# EVK-IRIS-W1-MCULINK_USB_DCDC.net
KiCad netlist of a schematic drawn in Altium Designer
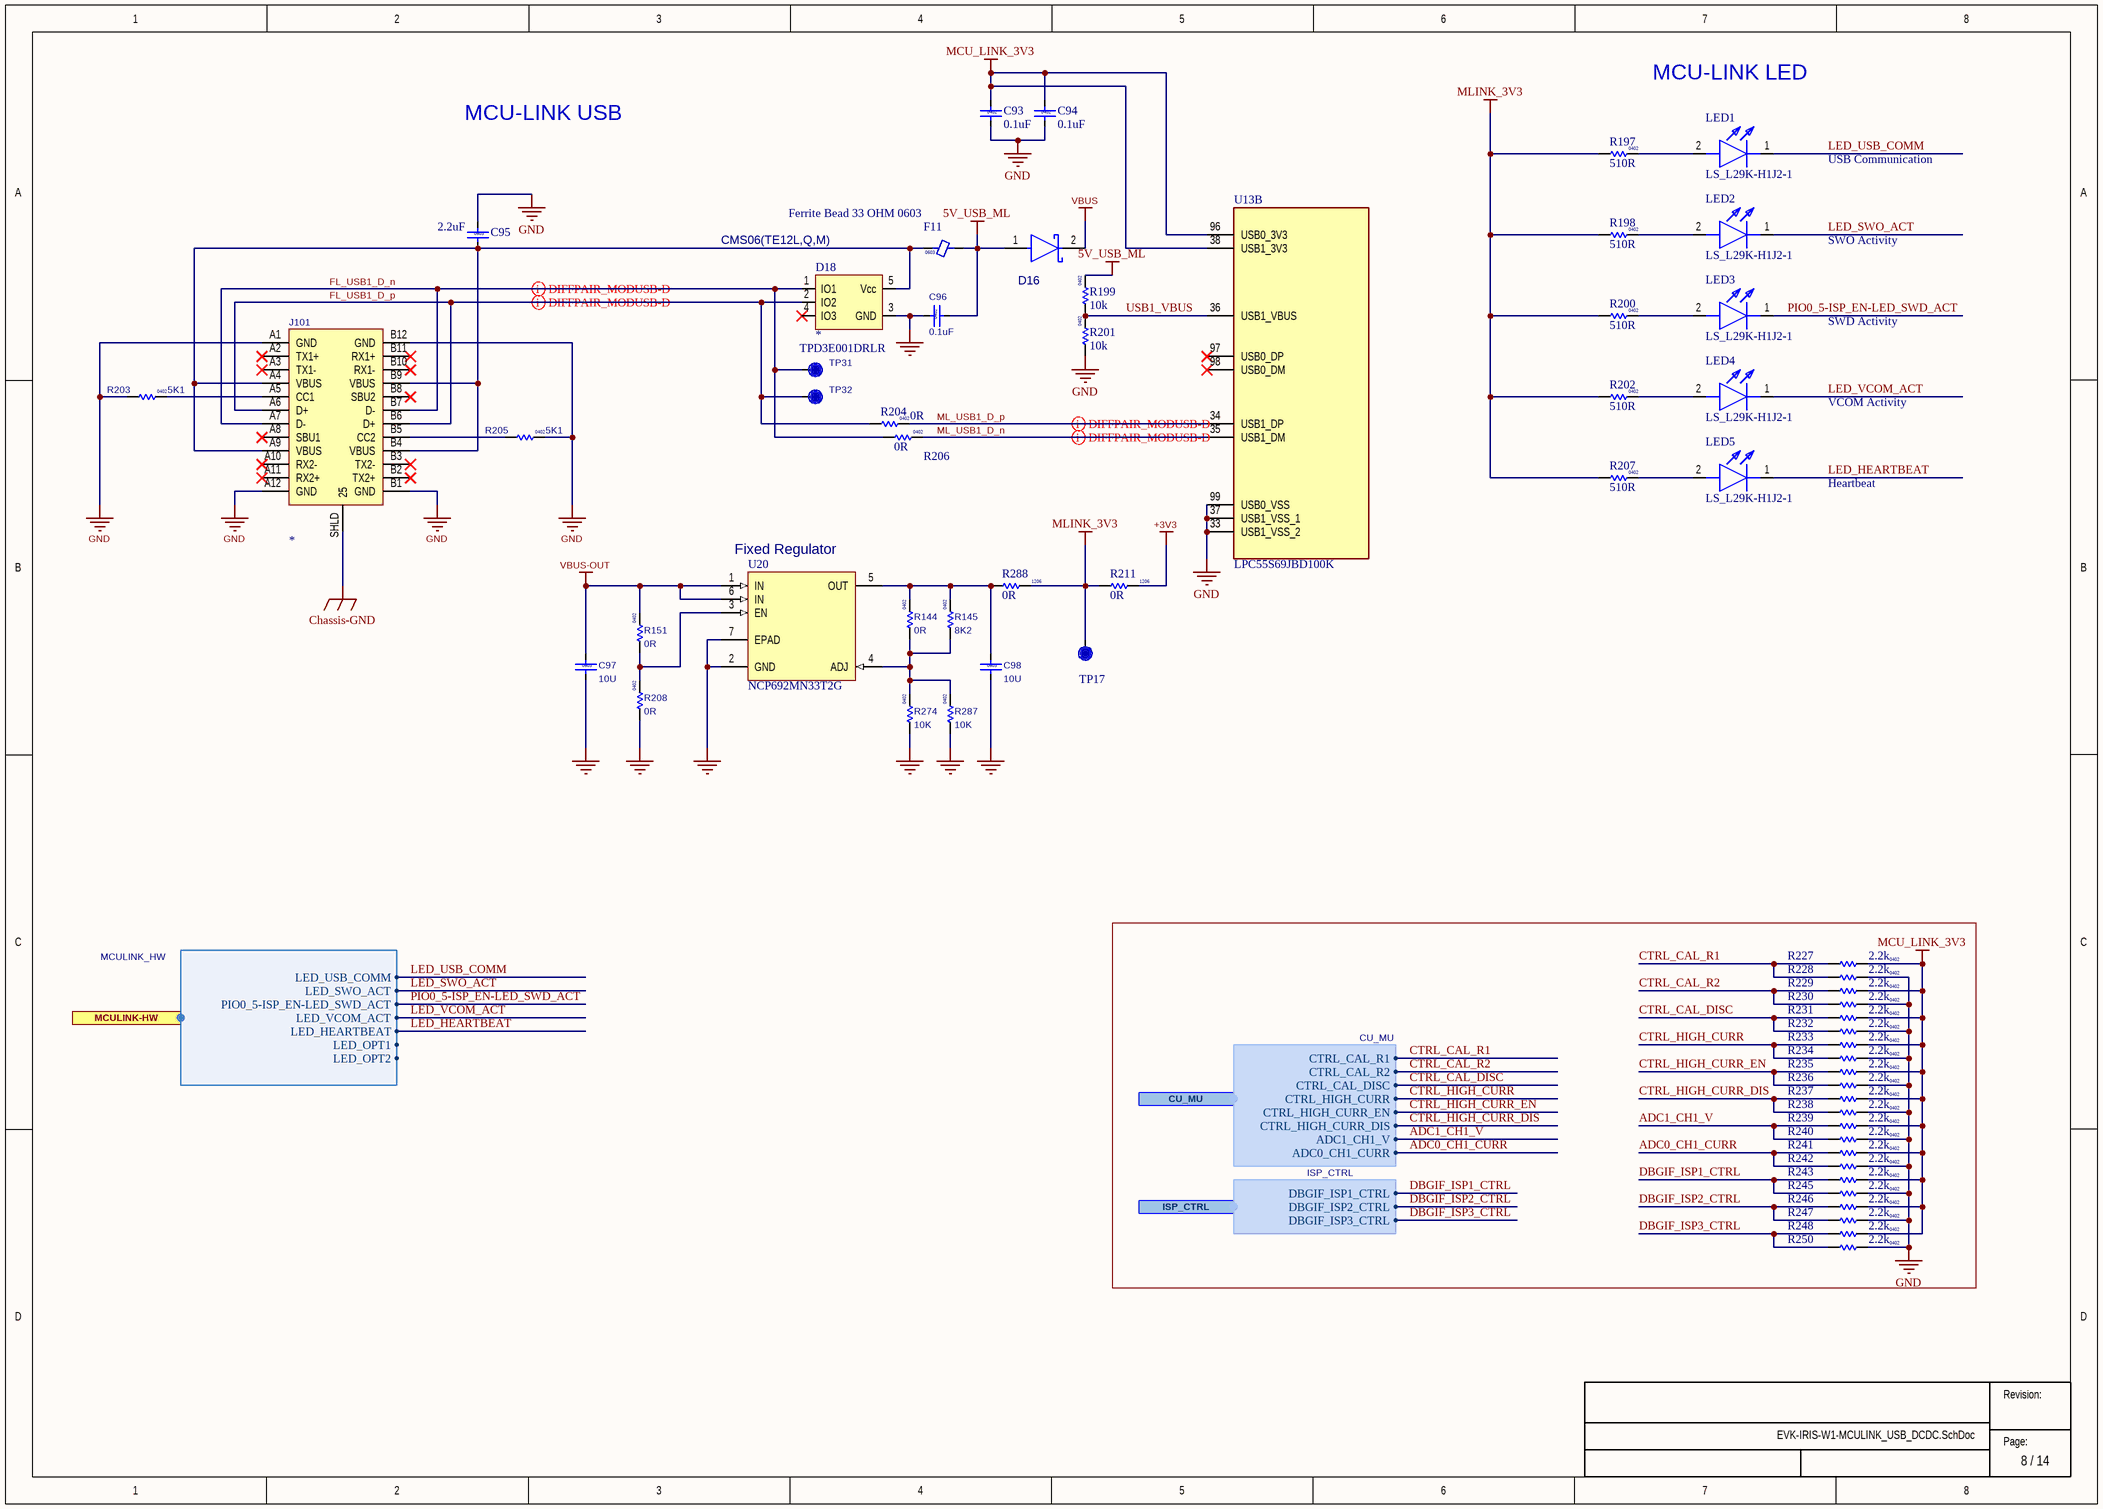
[diagram p0: EVK-IRIS-W1-MCULINK_USB_DCDC.SchDoc]

(export (version "E")
  (design (tool "Eeschema 10.0.6"))
  (components
    (comp (ref "C93")
      (value "0.1uF")
      (footprint "Cap 0402 HD")
      (description "Cap, Ceramic 0.1uF 10V 10% X5R 0402")
      (fields
        (field (name "SIZE") "0402")
        (field (name "PART NUMBER") "120-00016")
        (field (name "TOLERANCE") "+/- 10%")
      )
      (libsource (lib "Arena_Parts_DB_Lib") (part "Cap Chip"))
    )
    (comp (ref "C94")
      (value "0.1uF")
      (footprint "Cap 0402 HD")
      (description "Cap, Ceramic 0.1uF 10V 10% X5R 0402")
      (fields
        (field (name "SIZE") "0402")
        (field (name "PART NUMBER") "120-00016")
        (field (name "TOLERANCE") "+/- 10%")
      )
      (libsource (lib "Arena_Parts_DB_Lib") (part "Cap Chip"))
    )
    (comp (ref "C95")
      (value "2.2uF")
      (footprint "Cap 0603 HD")
      (description "Cap, Ceramic 2.2uF 10V 10% X5R 0603")
      (fields
        (field (name "SIZE") "0603")
        (field (name "PART NUMBER") "120-00004")
        (field (name "TOLERANCE") "+/- 10%")
      )
      (libsource (lib "Arena_Parts_DB_Lib") (part "Cap Chip"))
    )
    (comp (ref "C96")
      (value "0.1uF")
      (footprint "Cap 0402 HD")
      (description "Cap, Ceramic 0.1uF 10V 10% X5R 0402")
      (fields
        (field (name "SIZE") "0402")
        (field (name "PART NUMBER") "120-00016")
        (field (name "MANUFACTURER") "Murata Electronics North America")
      )
      (libsource (lib "Arena_Parts_DB_Lib") (part "Cap Chip"))
    )
    (comp (ref "C97")
      (value "10U")
      (footprint "Cap 0603 HD")
      (description "CAP CER X7R 0603 10U 20% 10V")
      (fields
        (field (name "SIZE") "0603")
        (field (name "PART NUMBER") "UBXH01-0000310")
        (field (name "TOLERANCE") "20%")
        (field (name "EDITOR") "michael.hein")
        (field (name "RELEASED BY") "martin.grasse")
      )
      (libsource (lib "UBX_Parts_DB_Lib") (part "Cap Chip"))
    )
    (comp (ref "C98")
      (value "10U")
      (footprint "Cap 0603 HD")
      (description "CAP CER X7R 0603 10U 20% 10V")
      (fields
        (field (name "SIZE") "0603")
        (field (name "PART NUMBER") "UBXH01-0000310")
        (field (name "TOLERANCE") "20%")
        (field (name "EDITOR") "michael.hein")
        (field (name "RELEASED BY") "martin.grasse")
      )
      (libsource (lib "UBX_Parts_DB_Lib") (part "Cap Chip"))
    )
    (comp (ref "D16")
      (value "CMS06(TE12L,Q,M)")
      (footprint "FP-M-FLAT-MFG")
      (description "Diode Schottky 30 V 2A Surface Mount M-FLAT (2.4x3.8)")
      (fields (field (name "MANUFACTURER") "Toshiba"))
      (libsource (lib "CMS06(TE12L,Q,M)") (part "360ad2f4ac25a952324d13796385471"))
    )
    (comp (ref "D18")
      (value "110-00018")
      (footprint "SOT-553")
      (description "TVS Diode, ESD High Speed 3-Channel Array, SOT-553")
      (fields
        (field (name "MANUFACTURER P/N") "*")
        (field (name "MANUFACTURER PART NUMBER 1") "TPD3E001DRLR")
        (field (name "VOLTAGE") "5.5V")
      )
      (libsource (lib "Arena_Parts_DB_Lib") (part "TPD3E001"))
    )
    (comp (ref "F11")
      (value "155-00012")
      (footprint "IND 0603")
      (description "FERRITE BEAD 33 OHM 0603 1LN")
      (fields
        (field (name "SIZE") "0603")
        (field (name "PART NAME") "Ferrite Bead 33 OHM 0603")
        (field (name "VOLTAGE") "None")
      )
      (libsource (lib "Arena_Parts_DB_Lib") (part "FB sm"))
    )
    (comp (ref "J101")
      (value "130-00150")
      (footprint "CON_USB-C-RA_W-6Tabs")
      (description "Connector, USB-C Receptacle, 24 Position, Surface Mount, Right Angle, Horizontal, 20V")
      (fields (field (name "MANUFACTURER P/N") "*") (field (name "VOLTAGE") "20V"))
      (libsource (lib "Arena_Parts_DB_Lib") (part "USB-24Pin_W-Shield"))
    )
    (comp (ref "LED1")
      (value "LS_L29K-H1J2-1")
      (footprint "SamacSys:SMT-0603")
      (description "LED")
      (fields
        (field (name "MANUFACTURER_PART_NUMBER") "LS L29K-H1J2-1")
        (field (name "MOUSER PART NUMBER") "720-LSL29K-H1J2-1-Z")
      )
      (libsource (lib "*") (part "LS_L29K-H1J2-1"))
    )
    (comp (ref "LED2")
      (value "LS_L29K-H1J2-1")
      (footprint "SamacSys:SMT-0603")
      (description "LED")
      (fields
        (field (name "MANUFACTURER_PART_NUMBER") "LS L29K-H1J2-1")
        (field (name "MOUSER PART NUMBER") "720-LSL29K-H1J2-1-Z")
      )
      (libsource (lib "*") (part "LS_L29K-H1J2-1"))
    )
    (comp (ref "LED3")
      (value "LS_L29K-H1J2-1")
      (footprint "SamacSys:SMT-0603")
      (description "LED")
      (fields
        (field (name "MANUFACTURER_PART_NUMBER") "LS L29K-H1J2-1")
        (field (name "MOUSER PART NUMBER") "720-LSL29K-H1J2-1-Z")
      )
      (libsource (lib "*") (part "LS_L29K-H1J2-1"))
    )
    (comp (ref "LED4")
      (value "LS_L29K-H1J2-1")
      (footprint "SamacSys:SMT-0603")
      (description "LED")
      (fields
        (field (name "MANUFACTURER_PART_NUMBER") "LS L29K-H1J2-1")
        (field (name "MOUSER PART NUMBER") "720-LSL29K-H1J2-1-Z")
      )
      (libsource (lib "*") (part "LS_L29K-H1J2-1"))
    )
    (comp (ref "LED5")
      (value "LS_L29K-H1J2-1")
      (footprint "SamacSys:SMT-0603")
      (description "LED")
      (fields
        (field (name "MANUFACTURER_PART_NUMBER") "LS L29K-H1J2-1")
        (field (name "MOUSER PART NUMBER") "720-LSL29K-H1J2-1-Z")
      )
      (libsource (lib "*") (part "LS_L29K-H1J2-1"))
    )
    (comp (ref "R144")
      (value "0R")
      (footprint "RES 0402 HD")
      (description "RES THICK FILM CHIP 0402 0R 0 100mW")
      (fields
        (field (name "SIZE") "0402")
        (field (name "PART NUMBER") "UBXH18-0003002")
        (field (name "TOLERANCE") "0")
        (field (name "EDITOR") "charlotte.biber")
        (field (name "RELEASED BY") "peter.mueller")
      )
      (libsource (lib "UBX_Parts_DB_Lib") (part "Res sm"))
    )
    (comp (ref "R145")
      (value "8K2")
      (footprint "RES 0402 HD")
      (description "RES THICK FILM CHIP 0402 8K2 1% 63mW")
      (fields
        (field (name "SIZE") "0402")
        (field (name "PART NUMBER") "UBXH18-0000138")
        (field (name "TOLERANCE") "1%")
        (field (name "EDITOR") "matej.budin")
        (field (name "RELEASED BY") "pasquale.scorca")
      )
      (libsource (lib "UBX_Parts_DB_Lib") (part "Res sm"))
    )
    (comp (ref "R151")
      (value "0R")
      (footprint "RES 0402 HD")
      (description "RES THICK FILM CHIP 0402 0R 0 100mW")
      (fields
        (field (name "SIZE") "0402")
        (field (name "PART NUMBER") "UBXH18-0003002")
        (field (name "TOLERANCE") "0")
        (field (name "EDITOR") "charlotte.biber")
        (field (name "RELEASED BY") "peter.mueller")
      )
      (libsource (lib "UBX_Parts_DB_Lib") (part "Res sm"))
    )
    (comp (ref "R197")
      (value "510R")
      (footprint "RES 0402 HD")
      (description "RES THICK FILM CHIP 0402 510R 5% 100mW")
      (fields
        (field (name "SIZE") "0402")
        (field (name "PART NUMBER") "UBXH18-0008042")
        (field (name "TOLERANCE") "5%")
        (field (name "EDITOR") "peter.mueller")
      )
      (libsource (lib "UBX_Parts_DB_Lib") (part "Res sm"))
    )
    (comp (ref "R198")
      (value "510R")
      (footprint "RES 0402 HD")
      (description "RES THICK FILM CHIP 0402 510R 5% 100mW")
      (fields
        (field (name "SIZE") "0402")
        (field (name "PART NUMBER") "UBXH18-0008042")
        (field (name "TOLERANCE") "5%")
        (field (name "EDITOR") "peter.mueller")
      )
      (libsource (lib "UBX_Parts_DB_Lib") (part "Res sm"))
    )
    (comp (ref "R199")
      (value "10k")
      (footprint "RES 0402 HD")
      (description "Resistor 10k ohm 1% 1/16W, 0402")
      (fields
        (field (name "SIZE") "0402")
        (field (name "PART NUMBER") "180-00024")
        (field (name "POWER") "1/16W")
      )
      (libsource (lib "Arena_Parts_DB_Lib") (part "Res sm"))
    )
    (comp (ref "R200")
      (value "510R")
      (footprint "RES 0402 HD")
      (description "RES THICK FILM CHIP 0402 510R 5% 100mW")
      (fields
        (field (name "SIZE") "0402")
        (field (name "PART NUMBER") "UBXH18-0008042")
        (field (name "TOLERANCE") "5%")
        (field (name "EDITOR") "peter.mueller")
      )
      (libsource (lib "UBX_Parts_DB_Lib") (part "Res sm"))
    )
    (comp (ref "R201")
      (value "10k")
      (footprint "RES 0402 HD")
      (description "Resistor 10k ohm 1% 1/16W, 0402")
      (fields
        (field (name "SIZE") "0402")
        (field (name "PART NUMBER") "180-00024")
        (field (name "POWER") "1/16W")
      )
      (libsource (lib "Arena_Parts_DB_Lib") (part "Res sm"))
    )
    (comp (ref "R202")
      (value "510R")
      (footprint "RES 0402 HD")
      (description "RES THICK FILM CHIP 0402 510R 5% 100mW")
      (fields
        (field (name "SIZE") "0402")
        (field (name "PART NUMBER") "UBXH18-0008042")
        (field (name "TOLERANCE") "5%")
        (field (name "EDITOR") "peter.mueller")
      )
      (libsource (lib "UBX_Parts_DB_Lib") (part "Res sm"))
    )
    (comp (ref "R203")
      (value "5K1")
      (footprint "RES 0402 HD")
      (description "RES THICK FILM CHIP 0402 5K1 5% 100mW")
      (fields
        (field (name "SIZE") "0402")
        (field (name "PART NUMBER") "UBXH18-0008066")
        (field (name "TOLERANCE") "5%")
        (field (name "EDITOR") "alvaro.nussbaum")
        (field (name "RELEASED BY") "roland.rust")
      )
      (libsource (lib "UBX_Parts_DB_Lib") (part "Res sm"))
    )
    (comp (ref "R204")
      (value "0R")
      (footprint "RES 0402 HD")
      (description "RES THICK FILM CHIP 0402 0R 0 100mW")
      (fields
        (field (name "SIZE") "0402")
        (field (name "PART NUMBER") "UBXH18-0003002")
        (field (name "TOLERANCE") "0")
        (field (name "EDITOR") "charlotte.biber")
        (field (name "RELEASED BY") "peter.mueller")
      )
      (libsource (lib "UBX_Parts_DB_Lib") (part "Res sm"))
    )
    (comp (ref "R205")
      (value "5K1")
      (footprint "RES 0402 HD")
      (description "RES THICK FILM CHIP 0402 5K1 5% 100mW")
      (fields
        (field (name "SIZE") "0402")
        (field (name "PART NUMBER") "UBXH18-0008066")
        (field (name "TOLERANCE") "5%")
        (field (name "EDITOR") "alvaro.nussbaum")
        (field (name "RELEASED BY") "roland.rust")
      )
      (libsource (lib "UBX_Parts_DB_Lib") (part "Res sm"))
    )
    (comp (ref "R206")
      (value "0R")
      (footprint "RES 0402 HD")
      (description "RES THICK FILM CHIP 0402 0R 0 100mW")
      (fields
        (field (name "SIZE") "0402")
        (field (name "PART NUMBER") "UBXH18-0003002")
        (field (name "TOLERANCE") "0")
        (field (name "EDITOR") "charlotte.biber")
        (field (name "RELEASED BY") "peter.mueller")
      )
      (libsource (lib "UBX_Parts_DB_Lib") (part "Res sm"))
    )
    (comp (ref "R207")
      (value "510R")
      (footprint "RES 0402 HD")
      (description "RES THICK FILM CHIP 0402 510R 5% 100mW")
      (fields
        (field (name "SIZE") "0402")
        (field (name "PART NUMBER") "UBXH18-0008042")
        (field (name "TOLERANCE") "5%")
        (field (name "EDITOR") "peter.mueller")
      )
      (libsource (lib "UBX_Parts_DB_Lib") (part "Res sm"))
    )
    (comp (ref "R208")
      (value "0R")
      (footprint "RES 0402 HD")
      (description "RES THICK FILM CHIP 0402 0R 0 100mW")
      (fields
        (field (name "SIZE") "0402")
        (field (name "PART NUMBER") "UBXH18-0003002")
        (field (name "TOLERANCE") "0")
        (field (name "EDITOR") "charlotte.biber")
        (field (name "RELEASED BY") "peter.mueller")
      )
      (libsource (lib "UBX_Parts_DB_Lib") (part "Res sm"))
    )
    (comp (ref "R211")
      (value "0R")
      (footprint "RES 1206")
      (description "RES THICK FILM CHIP 1206 0R 0 2A")
      (fields
        (field (name "SIZE") "1206")
        (field (name "PART NUMBER") "UBXH18-0000020")
        (field (name "TOLERANCE") "0")
        (field (name "EDITOR") "massimo.vlacci")
        (field (name "RELEASED BY") "erian.bezhani")
      )
      (libsource (lib "UBX_Parts_DB_Lib") (part "Res sm"))
    )
    (comp (ref "R227")
      (value "2.2k")
      (footprint "RES 0402 HD")
      (description "Resistor, 2.2Kohm, 1%, 1/16W, 0402")
      (fields
        (field (name "SIZE") "0402")
        (field (name "PART NUMBER") "180-00023")
        (field (name "POWER") "1/16W")
      )
      (libsource (lib "Arena_Parts_DB_Lib") (part "Res sm"))
    )
    (comp (ref "R228")
      (value "2.2k")
      (footprint "RES 0402 HD")
      (description "Resistor, 2.2Kohm, 1%, 1/16W, 0402")
      (fields
        (field (name "SIZE") "0402")
        (field (name "PART NUMBER") "180-00023")
        (field (name "POWER") "1/16W")
      )
      (libsource (lib "Arena_Parts_DB_Lib") (part "Res sm"))
    )
    (comp (ref "R229")
      (value "2.2k")
      (footprint "RES 0402 HD")
      (description "Resistor, 2.2Kohm, 1%, 1/16W, 0402")
      (fields
        (field (name "SIZE") "0402")
        (field (name "PART NUMBER") "180-00023")
        (field (name "POWER") "1/16W")
      )
      (libsource (lib "Arena_Parts_DB_Lib") (part "Res sm"))
    )
    (comp (ref "R230")
      (value "2.2k")
      (footprint "RES 0402 HD")
      (description "Resistor, 2.2Kohm, 1%, 1/16W, 0402")
      (fields
        (field (name "SIZE") "0402")
        (field (name "PART NUMBER") "180-00023")
        (field (name "POWER") "1/16W")
      )
      (libsource (lib "Arena_Parts_DB_Lib") (part "Res sm"))
    )
    (comp (ref "R231")
      (value "2.2k")
      (footprint "RES 0402 HD")
      (description "Resistor, 2.2Kohm, 1%, 1/16W, 0402")
      (fields
        (field (name "SIZE") "0402")
        (field (name "PART NUMBER") "180-00023")
        (field (name "POWER") "1/16W")
      )
      (libsource (lib "Arena_Parts_DB_Lib") (part "Res sm"))
    )
    (comp (ref "R232")
      (value "2.2k")
      (footprint "RES 0402 HD")
      (description "Resistor, 2.2Kohm, 1%, 1/16W, 0402")
      (fields
        (field (name "SIZE") "0402")
        (field (name "PART NUMBER") "180-00023")
        (field (name "POWER") "1/16W")
      )
      (libsource (lib "Arena_Parts_DB_Lib") (part "Res sm"))
    )
    (comp (ref "R233")
      (value "2.2k")
      (footprint "RES 0402 HD")
      (description "Resistor, 2.2Kohm, 1%, 1/16W, 0402")
      (fields
        (field (name "SIZE") "0402")
        (field (name "PART NUMBER") "180-00023")
        (field (name "POWER") "1/16W")
      )
      (libsource (lib "Arena_Parts_DB_Lib") (part "Res sm"))
    )
    (comp (ref "R234")
      (value "2.2k")
      (footprint "RES 0402 HD")
      (description "Resistor, 2.2Kohm, 1%, 1/16W, 0402")
      (fields
        (field (name "SIZE") "0402")
        (field (name "PART NUMBER") "180-00023")
        (field (name "POWER") "1/16W")
      )
      (libsource (lib "Arena_Parts_DB_Lib") (part "Res sm"))
    )
    (comp (ref "R235")
      (value "2.2k")
      (footprint "RES 0402 HD")
      (description "Resistor, 2.2Kohm, 1%, 1/16W, 0402")
      (fields
        (field (name "SIZE") "0402")
        (field (name "PART NUMBER") "180-00023")
        (field (name "POWER") "1/16W")
      )
      (libsource (lib "Arena_Parts_DB_Lib") (part "Res sm"))
    )
    (comp (ref "R236")
      (value "2.2k")
      (footprint "RES 0402 HD")
      (description "Resistor, 2.2Kohm, 1%, 1/16W, 0402")
      (fields
        (field (name "SIZE") "0402")
        (field (name "PART NUMBER") "180-00023")
        (field (name "POWER") "1/16W")
      )
      (libsource (lib "Arena_Parts_DB_Lib") (part "Res sm"))
    )
    (comp (ref "R237")
      (value "2.2k")
      (footprint "RES 0402 HD")
      (description "Resistor, 2.2Kohm, 1%, 1/16W, 0402")
      (fields
        (field (name "SIZE") "0402")
        (field (name "PART NUMBER") "180-00023")
        (field (name "POWER") "1/16W")
      )
      (libsource (lib "Arena_Parts_DB_Lib") (part "Res sm"))
    )
    (comp (ref "R238")
      (value "2.2k")
      (footprint "RES 0402 HD")
      (description "Resistor, 2.2Kohm, 1%, 1/16W, 0402")
      (fields
        (field (name "SIZE") "0402")
        (field (name "PART NUMBER") "180-00023")
        (field (name "POWER") "1/16W")
      )
      (libsource (lib "Arena_Parts_DB_Lib") (part "Res sm"))
    )
    (comp (ref "R239")
      (value "2.2k")
      (footprint "RES 0402 HD")
      (description "Resistor, 2.2Kohm, 1%, 1/16W, 0402")
      (fields
        (field (name "SIZE") "0402")
        (field (name "PART NUMBER") "180-00023")
        (field (name "POWER") "1/16W")
      )
      (libsource (lib "Arena_Parts_DB_Lib") (part "Res sm"))
    )
    (comp (ref "R240")
      (value "2.2k")
      (footprint "RES 0402 HD")
      (description "Resistor, 2.2Kohm, 1%, 1/16W, 0402")
      (fields
        (field (name "SIZE") "0402")
        (field (name "PART NUMBER") "180-00023")
        (field (name "POWER") "1/16W")
      )
      (libsource (lib "Arena_Parts_DB_Lib") (part "Res sm"))
    )
    (comp (ref "R241")
      (value "2.2k")
      (footprint "RES 0402 HD")
      (description "Resistor, 2.2Kohm, 1%, 1/16W, 0402")
      (fields
        (field (name "SIZE") "0402")
        (field (name "PART NUMBER") "180-00023")
        (field (name "POWER") "1/16W")
      )
      (libsource (lib "Arena_Parts_DB_Lib") (part "Res sm"))
    )
    (comp (ref "R242")
      (value "2.2k")
      (footprint "RES 0402 HD")
      (description "Resistor, 2.2Kohm, 1%, 1/16W, 0402")
      (fields
        (field (name "SIZE") "0402")
        (field (name "PART NUMBER") "180-00023")
        (field (name "POWER") "1/16W")
      )
      (libsource (lib "Arena_Parts_DB_Lib") (part "Res sm"))
    )
    (comp (ref "R243")
      (value "2.2k")
      (footprint "RES 0402 HD")
      (description "Resistor, 2.2Kohm, 1%, 1/16W, 0402")
      (fields
        (field (name "SIZE") "0402")
        (field (name "PART NUMBER") "180-00023")
        (field (name "POWER") "1/16W")
      )
      (libsource (lib "Arena_Parts_DB_Lib") (part "Res sm"))
    )
    (comp (ref "R245")
      (value "2.2k")
      (footprint "RES 0402 HD")
      (description "Resistor, 2.2Kohm, 1%, 1/16W, 0402")
      (fields
        (field (name "SIZE") "0402")
        (field (name "PART NUMBER") "180-00023")
        (field (name "POWER") "1/16W")
      )
      (libsource (lib "Arena_Parts_DB_Lib") (part "Res sm"))
    )
    (comp (ref "R246")
      (value "2.2k")
      (footprint "RES 0402 HD")
      (description "Resistor, 2.2Kohm, 1%, 1/16W, 0402")
      (fields
        (field (name "SIZE") "0402")
        (field (name "PART NUMBER") "180-00023")
        (field (name "POWER") "1/16W")
      )
      (libsource (lib "Arena_Parts_DB_Lib") (part "Res sm"))
    )
    (comp (ref "R247")
      (value "2.2k")
      (footprint "RES 0402 HD")
      (description "Resistor, 2.2Kohm, 1%, 1/16W, 0402")
      (fields
        (field (name "SIZE") "0402")
        (field (name "PART NUMBER") "180-00023")
        (field (name "POWER") "1/16W")
      )
      (libsource (lib "Arena_Parts_DB_Lib") (part "Res sm"))
    )
    (comp (ref "R248")
      (value "2.2k")
      (footprint "RES 0402 HD")
      (description "Resistor, 2.2Kohm, 1%, 1/16W, 0402")
      (fields
        (field (name "SIZE") "0402")
        (field (name "PART NUMBER") "180-00023")
        (field (name "POWER") "1/16W")
      )
      (libsource (lib "Arena_Parts_DB_Lib") (part "Res sm"))
    )
    (comp (ref "R250")
      (value "2.2k")
      (footprint "RES 0402 HD")
      (description "Resistor, 2.2Kohm, 1%, 1/16W, 0402")
      (fields
        (field (name "SIZE") "0402")
        (field (name "PART NUMBER") "180-00023")
        (field (name "POWER") "1/16W")
      )
      (libsource (lib "Arena_Parts_DB_Lib") (part "Res sm"))
    )
    (comp (ref "R274")
      (value "10K")
      (footprint "RES 0402 HD")
      (description "RES THICK FILM CHIP 0402 10K 1% 63mW")
      (fields
        (field (name "SIZE") "0402")
        (field (name "PART NUMBER") "UBXH18-0000065")
        (field (name "TOLERANCE") "1%")
        (field (name "EDITOR") "erian.bezhani")
        (field (name "RELEASED BY") "massimo.vlacci")
      )
      (libsource (lib "UBX_Parts_DB_Lib") (part "Res sm"))
    )
    (comp (ref "R287")
      (value "10K")
      (footprint "RES 0402 HD")
      (description "RES THICK FILM CHIP 0402 10K 1% 63mW")
      (fields
        (field (name "SIZE") "0402")
        (field (name "PART NUMBER") "UBXH18-0000065")
        (field (name "TOLERANCE") "1%")
        (field (name "EDITOR") "erian.bezhani")
        (field (name "RELEASED BY") "massimo.vlacci")
      )
      (libsource (lib "UBX_Parts_DB_Lib") (part "Res sm"))
    )
    (comp (ref "R288")
      (value "0R")
      (footprint "RES 1206")
      (description "RES THICK FILM CHIP 1206 0R 0 2A")
      (fields
        (field (name "SIZE") "1206")
        (field (name "PART NUMBER") "UBXH18-0000020")
        (field (name "TOLERANCE") "0")
        (field (name "EDITOR") "massimo.vlacci")
        (field (name "RELEASED BY") "erian.bezhani")
      )
      (libsource (lib "UBX_Parts_DB_Lib") (part "Res sm"))
    )
    (comp (ref "TP17")
      (value "TP")
      (footprint "TP10R")
      (description "Testpoint, Round 1.0mm Dia")
      (fields
        (field (name "PART NUMBER") "TP10R")
        (field (name "ADDED BY") "Jeremy D")
        (field (name "CHECKED BY") "Paul B")
      )
      (libsource (lib "LEGACY_Rigado_AltiumLib") (part "TP_R"))
    )
    (comp (ref "TP31")
      (value "TP")
      (footprint "TP10R")
      (description "Testpoint, Round 1.0mm Dia")
      (fields
        (field (name "PART NUMBER") "TP10R")
        (field (name "ADDED BY") "Jeremy D")
        (field (name "CHECKED BY") "Paul B")
      )
      (libsource (lib "LEGACY_Rigado_AltiumLib") (part "TP_R"))
    )
    (comp (ref "TP32")
      (value "TP")
      (footprint "TP10R")
      (description "Testpoint, Round 1.0mm Dia")
      (fields
        (field (name "PART NUMBER") "TP10R")
        (field (name "ADDED BY") "Jeremy D")
        (field (name "CHECKED BY") "Paul B")
      )
      (libsource (lib "LEGACY_Rigado_AltiumLib") (part "TP_R"))
    )
    (comp (ref "U13")
      (value "LPC55S69JBD100K")
      (footprint "QFP50P1600X1600X160-101N")
      (description "NXP - LPC55S69JBD100K - MCU, 32BIT, 100MHZ, HLQFP")
      (fields (field (name "MOUSER PART NUMBER") "771-LPC55S69JBD100K"))
      (libsource (lib "LPC55S69JBD100K") (part "LPC55S69JBD100K"))
    )
    (comp (ref "U20")
      (value "NCP692MN33T2G")
      (footprint "DFN-PSON.1P3X3-7pin_HS-7N")
      (description "LOW DROPOUT REGULATOR ON SEMICONDUCTOR NCP692MN33T2G 6DFN 3.3V 6V 1A")
      (fields
        (field (name "PART NUMBER") "UBXH12-0000459")
        (field (name "MANUFACTURER") "ON Semiconductor")
        (field (name "EDITOR") "hakan.ekfors")
        (field (name "RELEASED BY") "markus.wejrot")
      )
      (libsource (lib "UBX_Parts_DB_Lib") (part "NCP692MN33T2G"))
    )
  )
  (nets
    (net (code "4") (name "+3V3") (class "Default")
      (node (ref "R211") (pin "2") (pinfunction "2_2") (pintype "passive"))
    )
    (net (code "5") (name "/ADC0_CH1_CURR") (class "Default")
      (node (ref "R241") (pin "1") (pinfunction "1_1") (pintype "passive"))
      (node (ref "R242") (pin "1") (pinfunction "1_1") (pintype "passive"))
    )
    (net (code "6") (name "/ADC1_CH1_V") (class "Default")
      (node (ref "R239") (pin "1") (pinfunction "1_1") (pintype "passive"))
      (node (ref "R240") (pin "2") (pinfunction "2_2") (pintype "passive"))
    )
    (net (code "7") (name "/CTRL_CAL_DISC") (class "Default")
      (node (ref "R231") (pin "1") (pinfunction "1_1") (pintype "passive"))
      (node (ref "R232") (pin "2") (pinfunction "2_2") (pintype "passive"))
    )
    (net (code "8") (name "/CTRL_CAL_R1") (class "Default")
      (node (ref "R227") (pin "1") (pinfunction "1_1") (pintype "passive"))
      (node (ref "R228") (pin "2") (pinfunction "2_2") (pintype "passive"))
    )
    (net (code "9") (name "/CTRL_CAL_R2") (class "Default")
      (node (ref "R229") (pin "1") (pinfunction "1_1") (pintype "passive"))
      (node (ref "R230") (pin "1") (pinfunction "1_1") (pintype "passive"))
    )
    (net (code "10") (name "/CTRL_HIGH_CURR") (class "Default")
      (node (ref "R233") (pin "1") (pinfunction "1_1") (pintype "passive"))
      (node (ref "R234") (pin "1") (pinfunction "1_1") (pintype "passive"))
    )
    (net (code "11") (name "/CTRL_HIGH_CURR_DIS") (class "Default")
      (node (ref "R237") (pin "1") (pinfunction "1_1") (pintype "passive"))
      (node (ref "R238") (pin "1") (pinfunction "1_1") (pintype "passive"))
    )
    (net (code "12") (name "/CTRL_HIGH_CURR_EN") (class "Default")
      (node (ref "R235") (pin "1") (pinfunction "1_1") (pintype "passive"))
      (node (ref "R236") (pin "2") (pinfunction "2_2") (pintype "passive"))
    )
    (net (code "13") (name "/DBGIF_ISP1_CTRL") (class "Default")
      (node (ref "R243") (pin "1") (pinfunction "1_1") (pintype "passive"))
      (node (ref "R245") (pin "2") (pinfunction "2_2") (pintype "passive"))
    )
    (net (code "14") (name "/DBGIF_ISP2_CTRL") (class "Default")
      (node (ref "R246") (pin "1") (pinfunction "1_1") (pintype "passive"))
      (node (ref "R247") (pin "1") (pinfunction "1_1") (pintype "passive"))
    )
    (net (code "15") (name "/DBGIF_ISP3_CTRL") (class "Default")
      (node (ref "R248") (pin "1") (pinfunction "1_1") (pintype "passive"))
      (node (ref "R250") (pin "2") (pinfunction "2_2") (pintype "passive"))
    )
    (net (code "16") (name "/FL_USB1_D_n") (class "Default")
      (node (ref "D18") (pin "1") (pinfunction "IO1_1") (pintype "passive"))
      (node (ref "J101") (pin "A7") (pinfunction "D-_A7") (pintype "passive"))
      (node (ref "J101") (pin "B7") (pinfunction "D-_B7") (pintype "passive"))
      (node (ref "R206") (pin "1") (pinfunction "1_1") (pintype "passive"))
      (node (ref "TP31") (pin "1") (pintype "passive"))
    )
    (net (code "17") (name "/FL_USB1_D_p") (class "Default")
      (node (ref "D18") (pin "2") (pinfunction "IO2_2") (pintype "passive"))
      (node (ref "J101") (pin "A6") (pinfunction "D+_A6") (pintype "passive"))
      (node (ref "J101") (pin "B6") (pinfunction "D+_B6") (pintype "passive"))
      (node (ref "R204") (pin "1") (pinfunction "1_1") (pintype "passive"))
      (node (ref "TP32") (pin "1") (pintype "passive"))
    )
    (net (code "18") (name "/LED_HEARTBEAT") (class "Default")
      (node (ref "LED5") (pin "1") (pinfunction "K_1") (pintype "passive"))
    )
    (net (code "19") (name "/LED_SWO_ACT") (class "Default")
      (node (ref "LED2") (pin "1") (pinfunction "K_1") (pintype "passive"))
    )
    (net (code "20") (name "/LED_USB_COMM") (class "Default")
      (node (ref "LED1") (pin "1") (pinfunction "K_1") (pintype "passive"))
    )
    (net (code "21") (name "/LED_VCOM_ACT") (class "Default")
      (node (ref "LED4") (pin "1") (pinfunction "K_1") (pintype "passive"))
    )
    (net (code "22") (name "/ML_USB1_D_n") (class "Default")
      (node (ref "R206") (pin "2") (pinfunction "2_2") (pintype "passive"))
      (node (ref "U13") (pin "35") (pinfunction "USB1_DM_35") (pintype "passive"))
    )
    (net (code "23") (name "/ML_USB1_D_p") (class "Default")
      (node (ref "R204") (pin "2") (pinfunction "2_2") (pintype "passive"))
      (node (ref "U13") (pin "34") (pinfunction "USB1_DP_34") (pintype "passive"))
    )
    (net (code "24") (name "/PIO0_5-ISP_EN-LED_SWD_ACT") (class "Default")
      (node (ref "LED3") (pin "1") (pinfunction "K_1") (pintype "passive"))
    )
    (net (code "25") (name "/USB1_VBUS") (class "Default")
      (node (ref "R199") (pin "1") (pinfunction "1_1") (pintype "passive"))
      (node (ref "R201") (pin "2") (pinfunction "2_2") (pintype "passive"))
      (node (ref "U13") (pin "36") (pinfunction "USB1_VBUS_36") (pintype "passive"))
    )
    (net (code "29") (name "5V_USB_ML") (class "Default")
      (node (ref "C96") (pin "2") (pinfunction "2_2") (pintype "passive"))
      (node (ref "D16") (pin "1") (pinfunction "A_1") (pintype "passive"))
      (node (ref "F11") (pin "1") (pinfunction "1_1") (pintype "passive"))
      (node (ref "R199") (pin "2") (pinfunction "2_2") (pintype "passive"))
    )
    (net (code "30") (name "Chassis-GND") (class "Default")
      (node (ref "J101") (pin "SHLD") (pinfunction "25_SHLD") (pintype "passive"))
    )
    (net (code "31") (name "GND") (class "Default")
      (node (ref "C93") (pin "2") (pinfunction "2_2") (pintype "passive"))
      (node (ref "C94") (pin "2") (pinfunction "2_2") (pintype "passive"))
      (node (ref "C95") (pin "1") (pinfunction "1_1") (pintype "passive"))
      (node (ref "C96") (pin "1") (pinfunction "1_1") (pintype "passive"))
      (node (ref "C97") (pin "2") (pinfunction "2_2") (pintype "passive"))
      (node (ref "C98") (pin "2") (pinfunction "2_2") (pintype "passive"))
      (node (ref "D18") (pin "3") (pinfunction "GND_3") (pintype "power_in"))
      (node (ref "J101") (pin "A1") (pinfunction "GND_A1") (pintype "passive"))
      (node (ref "J101") (pin "A12") (pinfunction "GND_A12") (pintype "passive"))
      (node (ref "J101") (pin "B1") (pinfunction "GND_B1") (pintype "passive"))
      (node (ref "J101") (pin "B12") (pinfunction "GND_B12") (pintype "passive"))
      (node (ref "R201") (pin "1") (pinfunction "1_1") (pintype "passive"))
      (node (ref "R203") (pin "1") (pinfunction "1_1") (pintype "passive"))
      (node (ref "R205") (pin "2") (pinfunction "2_2") (pintype "passive"))
      (node (ref "R208") (pin "1") (pinfunction "1_1") (pintype "passive"))
      (node (ref "R228") (pin "1") (pinfunction "1_1") (pintype "passive"))
      (node (ref "R230") (pin "2") (pinfunction "2_2") (pintype "passive"))
      (node (ref "R232") (pin "1") (pinfunction "1_1") (pintype "passive"))
      (node (ref "R234") (pin "2") (pinfunction "2_2") (pintype "passive"))
      (node (ref "R236") (pin "1") (pinfunction "1_1") (pintype "passive"))
      (node (ref "R238") (pin "2") (pinfunction "2_2") (pintype "passive"))
      (node (ref "R240") (pin "1") (pinfunction "1_1") (pintype "passive"))
      (node (ref "R242") (pin "2") (pinfunction "2_2") (pintype "passive"))
      (node (ref "R245") (pin "1") (pinfunction "1_1") (pintype "passive"))
      (node (ref "R247") (pin "2") (pinfunction "2_2") (pintype "passive"))
      (node (ref "R250") (pin "1") (pinfunction "1_1") (pintype "passive"))
      (node (ref "R274") (pin "1") (pinfunction "1_1") (pintype "passive"))
      (node (ref "R287") (pin "1") (pinfunction "1_1") (pintype "passive"))
      (node (ref "U13") (pin "33") (pinfunction "USB1_VSS_2_33") (pintype "passive"))
      (node (ref "U13") (pin "37") (pinfunction "USB1_VSS_1_37") (pintype "passive"))
      (node (ref "U13") (pin "99") (pinfunction "USB0_VSS_99") (pintype "passive"))
      (node (ref "U20") (pin "2") (pinfunction "GND_2") (pintype "power_in"))
      (node (ref "U20") (pin "7") (pinfunction "EPAD_7") (pintype "power_in"))
    )
    (net (code "32") (name "MCU_LINK_3V3") (class "Default")
      (node (ref "C93") (pin "1") (pinfunction "1_1") (pintype "passive"))
      (node (ref "C94") (pin "1") (pinfunction "1_1") (pintype "passive"))
      (node (ref "R227") (pin "2") (pinfunction "2_2") (pintype "passive"))
      (node (ref "R229") (pin "2") (pinfunction "2_2") (pintype "passive"))
      (node (ref "R231") (pin "2") (pinfunction "2_2") (pintype "passive"))
      (node (ref "R233") (pin "2") (pinfunction "2_2") (pintype "passive"))
      (node (ref "R235") (pin "2") (pinfunction "2_2") (pintype "passive"))
      (node (ref "R237") (pin "2") (pinfunction "2_2") (pintype "passive"))
      (node (ref "R239") (pin "2") (pinfunction "2_2") (pintype "passive"))
      (node (ref "R241") (pin "2") (pinfunction "2_2") (pintype "passive"))
      (node (ref "R243") (pin "2") (pinfunction "2_2") (pintype "passive"))
      (node (ref "R246") (pin "2") (pinfunction "2_2") (pintype "passive"))
      (node (ref "R248") (pin "2") (pinfunction "2_2") (pintype "passive"))
      (node (ref "U13") (pin "38") (pinfunction "USB1_3V3_38") (pintype "passive"))
      (node (ref "U13") (pin "96") (pinfunction "USB0_3V3_96") (pintype "passive"))
    )
    (net (code "33") (name "MLINK_3V3") (class "Default")
      (node (ref "R197") (pin "1") (pinfunction "1_1") (pintype "passive"))
      (node (ref "R198") (pin "1") (pinfunction "1_1") (pintype "passive"))
      (node (ref "R200") (pin "1") (pinfunction "1_1") (pintype "passive"))
      (node (ref "R202") (pin "1") (pinfunction "1_1") (pintype "passive"))
      (node (ref "R207") (pin "1") (pinfunction "1_1") (pintype "passive"))
      (node (ref "R211") (pin "1") (pinfunction "1_1") (pintype "passive"))
      (node (ref "R288") (pin "2") (pinfunction "2_2") (pintype "passive"))
      (node (ref "TP17") (pin "1") (pintype "passive"))
    )
    (net (code "34") (name "Net-(D18-Vcc)") (class "Default")
      (node (ref "C95") (pin "2") (pinfunction "2_2") (pintype "passive"))
      (node (ref "D18") (pin "5") (pinfunction "Vcc_5") (pintype "power_in"))
      (node (ref "F11") (pin "2") (pinfunction "2_2") (pintype "passive"))
      (node (ref "J101") (pin "A4") (pinfunction "VBUS_A4") (pintype "passive"))
      (node (ref "J101") (pin "A9") (pinfunction "VBUS_A9") (pintype "passive"))
      (node (ref "J101") (pin "B4") (pinfunction "VBUS_B4") (pintype "passive"))
      (node (ref "J101") (pin "B9") (pinfunction "VBUS_B9") (pintype "passive"))
    )
    (net (code "35") (name "Net-(J101-CC1)") (class "Default")
      (node (ref "J101") (pin "A5") (pinfunction "CC1_A5") (pintype "passive"))
      (node (ref "R203") (pin "2") (pinfunction "2_2") (pintype "passive"))
    )
    (net (code "36") (name "Net-(J101-CC2)") (class "Default")
      (node (ref "J101") (pin "B5") (pinfunction "CC2_B5") (pintype "passive"))
      (node (ref "R205") (pin "1") (pinfunction "1_1") (pintype "passive"))
    )
    (net (code "37") (name "Net-(LED1-A)") (class "Default")
      (node (ref "LED1") (pin "2") (pinfunction "A_2") (pintype "passive"))
      (node (ref "R197") (pin "2") (pinfunction "2_2") (pintype "passive"))
    )
    (net (code "38") (name "Net-(LED2-A)") (class "Default")
      (node (ref "LED2") (pin "2") (pinfunction "A_2") (pintype "passive"))
      (node (ref "R198") (pin "2") (pinfunction "2_2") (pintype "passive"))
    )
    (net (code "39") (name "Net-(LED3-A)") (class "Default")
      (node (ref "LED3") (pin "2") (pinfunction "A_2") (pintype "passive"))
      (node (ref "R200") (pin "2") (pinfunction "2_2") (pintype "passive"))
    )
    (net (code "40") (name "Net-(LED4-A)") (class "Default")
      (node (ref "LED4") (pin "2") (pinfunction "A_2") (pintype "passive"))
      (node (ref "R202") (pin "2") (pinfunction "2_2") (pintype "passive"))
    )
    (net (code "41") (name "Net-(LED5-A)") (class "Default")
      (node (ref "LED5") (pin "2") (pinfunction "A_2") (pintype "passive"))
      (node (ref "R207") (pin "2") (pinfunction "2_2") (pintype "passive"))
    )
    (net (code "42") (name "Net-(U20-ADJ)") (class "Default")
      (node (ref "R144") (pin "1") (pinfunction "1_1") (pintype "passive"))
      (node (ref "R145") (pin "1") (pinfunction "1_1") (pintype "passive"))
      (node (ref "R274") (pin "2") (pinfunction "2_2") (pintype "passive"))
      (node (ref "R287") (pin "2") (pinfunction "2_2") (pintype "passive"))
      (node (ref "U20") (pin "4") (pinfunction "ADJ_4") (pintype "input"))
    )
    (net (code "43") (name "Net-(U20-EN)") (class "Default")
      (node (ref "R151") (pin "1") (pinfunction "1_1") (pintype "passive"))
      (node (ref "R208") (pin "2") (pinfunction "2_2") (pintype "passive"))
      (node (ref "U20") (pin "3") (pinfunction "EN_3") (pintype "input"))
    )
    (net (code "44") (name "Net-(U20-OUT)") (class "Default")
      (node (ref "C98") (pin "1") (pinfunction "1_1") (pintype "passive"))
      (node (ref "R144") (pin "2") (pinfunction "2_2") (pintype "passive"))
      (node (ref "R145") (pin "2") (pinfunction "2_2") (pintype "passive"))
      (node (ref "R288") (pin "1") (pinfunction "1_1") (pintype "passive"))
      (node (ref "U20") (pin "5") (pinfunction "OUT_5") (pintype "power_in"))
    )
    (net (code "45") (name "VBUS") (class "Default")
      (node (ref "D16") (pin "2") (pinfunction "C_2") (pintype "passive"))
    )
    (net (code "46") (name "VBUS-OUT") (class "Default")
      (node (ref "C97") (pin "1") (pinfunction "1_1") (pintype "passive"))
      (node (ref "R151") (pin "2") (pinfunction "2_2") (pintype "passive"))
      (node (ref "U20") (pin "1") (pinfunction "IN_1") (pintype "input"))
      (node (ref "U20") (pin "6") (pinfunction "IN_6") (pintype "input"))
    )
    (net (code "47") (name "unconnected-(D18-IO3-Pad4)") (class "Default")
      (node (ref "D18") (pin "4") (pinfunction "IO3_4") (pintype "passive+no_connect"))
    )
    (net (code "48") (name "unconnected-(J101-RX1+-PadB11)") (class "Default")
      (node (ref "J101") (pin "B11") (pinfunction "RX1+_B11") (pintype "passive+no_connect"))
    )
    (net (code "49") (name "unconnected-(J101-RX1--PadB10)") (class "Default")
      (node (ref "J101") (pin "B10") (pinfunction "RX1-_B10") (pintype "passive+no_connect"))
    )
    (net (code "50") (name "unconnected-(J101-RX2+-PadA11)") (class "Default")
      (node (ref "J101") (pin "A11") (pinfunction "RX2+_A11") (pintype "passive+no_connect"))
    )
    (net (code "51") (name "unconnected-(J101-RX2--PadA10)") (class "Default")
      (node (ref "J101") (pin "A10") (pinfunction "RX2-_A10") (pintype "passive+no_connect"))
    )
    (net (code "52") (name "unconnected-(J101-SBU1-PadA8)") (class "Default")
      (node (ref "J101") (pin "A8") (pinfunction "SBU1_A8") (pintype "passive+no_connect"))
    )
    (net (code "53") (name "unconnected-(J101-SBU2-PadB8)") (class "Default")
      (node (ref "J101") (pin "B8") (pinfunction "SBU2_B8") (pintype "passive+no_connect"))
    )
    (net (code "54") (name "unconnected-(J101-TX1+-PadA2)") (class "Default")
      (node (ref "J101") (pin "A2") (pinfunction "TX1+_A2") (pintype "passive+no_connect"))
    )
    (net (code "55") (name "unconnected-(J101-TX1--PadA3)") (class "Default")
      (node (ref "J101") (pin "A3") (pinfunction "TX1-_A3") (pintype "passive+no_connect"))
    )
    (net (code "56") (name "unconnected-(J101-TX2+-PadB2)") (class "Default")
      (node (ref "J101") (pin "B2") (pinfunction "TX2+_B2") (pintype "passive+no_connect"))
    )
    (net (code "57") (name "unconnected-(J101-TX2--PadB3)") (class "Default")
      (node (ref "J101") (pin "B3") (pinfunction "TX2-_B3") (pintype "passive+no_connect"))
    )
    (net (code "58") (name "unconnected-(U13B-USB0_DM-Pad98)") (class "Default")
      (node (ref "U13") (pin "98") (pinfunction "USB0_DM_98") (pintype "passive+no_connect"))
    )
    (net (code "59") (name "unconnected-(U13B-USB0_DP-Pad97)") (class "Default")
      (node (ref "U13") (pin "97") (pinfunction "USB0_DP_97") (pintype "passive+no_connect"))
    )
  )
)
